# LED_Driver.net
KiCad netlist of a schematic drawn in Altium Designer
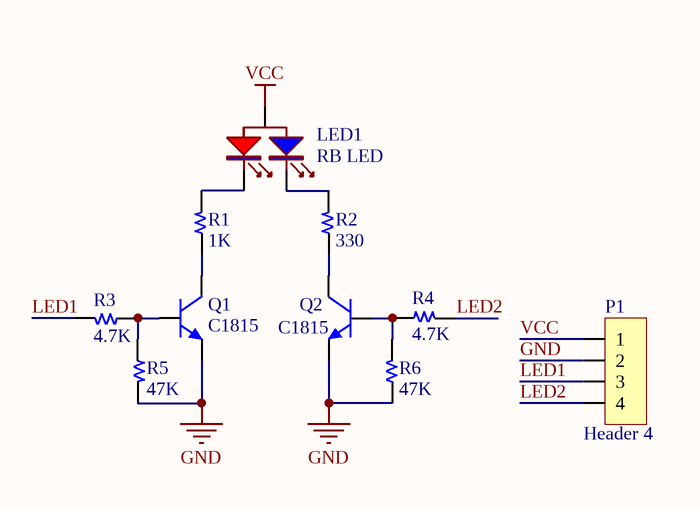
[diagram p0: LED_Driver.SchDoc]

(export (version "E")
  (design (tool "Eeschema 10.0.6"))
  (components
    (comp (ref "LED1")
      (value "RB LED")
      (footprint "LED-BICOLOR-3MM")
      (description "Bicolor RB 3mm LED")
      (libsource (lib "chipfc_altium_libs") (part "LED 2-color-A"))
    )
    (comp (ref "P1")
      (value "Header 4")
      (footprint "HDR/Header/4/BOX/RED")
      (description "Header, 4-Pin")
      (libsource (lib "chipfc_altium_libs") (part "Header 4"))
    )
    (comp (ref "Q1")
      (value "C1815")
      (footprint "SOT-23")
      (description "NPN Bipolar Transistor")
      (libsource (lib "chipfc_altium_libs") (part "Transistor NPN"))
    )
    (comp (ref "Q2")
      (value "C1815")
      (footprint "SOT-23")
      (description "NPN Bipolar Transistor")
      (libsource (lib "chipfc_altium_libs") (part "Transistor NPN"))
    )
    (comp (ref "R1")
      (value "1K")
      (footprint "R 0603")
      (description "Resistor")
      (libsource (lib "chipfc_altium_libs") (part "Resistor"))
    )
    (comp (ref "R2")
      (value "330")
      (footprint "R 0603")
      (description "Resistor")
      (libsource (lib "chipfc_altium_libs") (part "Resistor"))
    )
    (comp (ref "R3")
      (value "4.7K")
      (footprint "R 0603")
      (description "Resistor")
      (libsource (lib "chipfc_altium_libs") (part "Resistor"))
    )
    (comp (ref "R4")
      (value "4.7K")
      (footprint "R 0603")
      (description "Resistor")
      (libsource (lib "chipfc_altium_libs") (part "Resistor"))
    )
    (comp (ref "R5")
      (value "47K")
      (footprint "R 0603")
      (description "Resistor")
      (libsource (lib "chipfc_altium_libs") (part "Resistor"))
    )
    (comp (ref "R6")
      (value "47K")
      (footprint "R 0603")
      (description "Resistor")
      (libsource (lib "chipfc_altium_libs") (part "Resistor"))
    )
  )
  (nets
    (net (code "1") (name "/LED1") (class "Default")
      (node (ref "P1") (pin "3") (pinfunction "3_3") (pintype "passive"))
      (node (ref "R3") (pin "2") (pinfunction "2_2") (pintype "passive"))
    )
    (net (code "2") (name "/LED2") (class "Default")
      (node (ref "P1") (pin "4") (pinfunction "4_4") (pintype "passive"))
      (node (ref "R4") (pin "1") (pinfunction "1_1") (pintype "passive"))
    )
    (net (code "3") (name "GND") (class "Default")
      (node (ref "P1") (pin "2") (pinfunction "2_2") (pintype "passive"))
      (node (ref "Q1") (pin "2") (pinfunction "E_2") (pintype "passive"))
      (node (ref "Q2") (pin "2") (pinfunction "E_2") (pintype "passive"))
      (node (ref "R5") (pin "2") (pinfunction "2_2") (pintype "passive"))
      (node (ref "R6") (pin "2") (pinfunction "2_2") (pintype "passive"))
    )
    (net (code "4") (name "Net-(LED1-K1)") (class "Default")
      (node (ref "LED1") (pin "1") (pinfunction "K1_1") (pintype "passive"))
      (node (ref "R1") (pin "2") (pinfunction "2_2") (pintype "passive"))
    )
    (net (code "5") (name "Net-(LED1-K2)") (class "Default")
      (node (ref "LED1") (pin "3") (pinfunction "K2_3") (pintype "passive"))
      (node (ref "R2") (pin "2") (pinfunction "2_2") (pintype "passive"))
    )
    (net (code "6") (name "Net-(Q1-B)") (class "Default")
      (node (ref "Q1") (pin "1") (pinfunction "B_1") (pintype "passive"))
      (node (ref "R3") (pin "1") (pinfunction "1_1") (pintype "passive"))
      (node (ref "R5") (pin "1") (pinfunction "1_1") (pintype "passive"))
    )
    (net (code "7") (name "Net-(Q1-C)") (class "Default")
      (node (ref "Q1") (pin "3") (pinfunction "C_3") (pintype "passive"))
      (node (ref "R1") (pin "1") (pinfunction "1_1") (pintype "passive"))
    )
    (net (code "8") (name "Net-(Q2-B)") (class "Default")
      (node (ref "Q2") (pin "1") (pinfunction "B_1") (pintype "passive"))
      (node (ref "R4") (pin "2") (pinfunction "2_2") (pintype "passive"))
      (node (ref "R6") (pin "1") (pinfunction "1_1") (pintype "passive"))
    )
    (net (code "9") (name "Net-(Q2-C)") (class "Default")
      (node (ref "Q2") (pin "3") (pinfunction "C_3") (pintype "passive"))
      (node (ref "R2") (pin "1") (pinfunction "1_1") (pintype "passive"))
    )
    (net (code "10") (name "VCC") (class "Default")
      (node (ref "LED1") (pin "2") (pinfunction "A_2") (pintype "passive"))
      (node (ref "P1") (pin "1") (pinfunction "1_1") (pintype "passive"))
    )
  )
)
